# temp_sensor.net
KiCad netlist of a schematic drawn in EAGLE
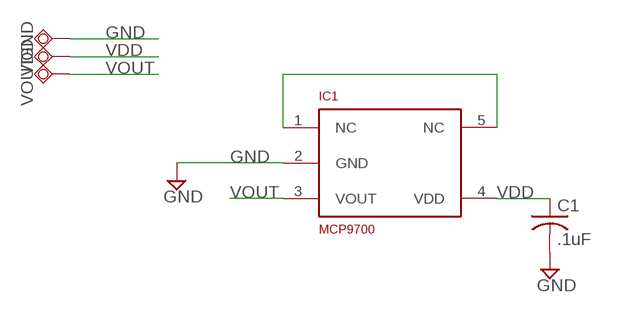
[diagram p0: schematic, sheet 1]

(export (version "E")
  (design (tool "Eeschema 10.0.6"))
  (components
    (comp (ref "C1")
      (value ".1uF")
      (footprint "eagle-import:C0805K")
      (libsource (lib "eagle-import") (part "C-USC0805K"))
    )
    (comp (ref "GND")
      (value "TPSQTP20SQ")
      (footprint "eagle-import:TP20SQ")
      (libsource (lib "eagle-import") (part "TPSQTP20SQ"))
    )
    (comp (ref "IC1")
      (value "MCP9700")
      (footprint "eagle-import:SC70")
      (libsource (lib "eagle-import") (part "MCP9700"))
    )
    (comp (ref "VDD")
      (value "TPSQTP20SQ")
      (footprint "eagle-import:TP20SQ")
      (libsource (lib "eagle-import") (part "TPSQTP20SQ"))
    )
    (comp (ref "VOUT")
      (value "TPSQTP20SQ")
      (footprint "eagle-import:TP20SQ")
      (libsource (lib "eagle-import") (part "TPSQTP20SQ"))
    )
  )
  (nets
    (net (code "1") (name "/VDD") (class "Default")
      (node (ref "C1") (pin "1") (pinfunction "1_1") (pintype "passive"))
      (node (ref "IC1") (pin "4") (pinfunction "VDD_4") (pintype "bidirectional"))
      (node (ref "VDD") (pin "TP") (pinfunction "TP_TP") (pintype "input"))
    )
    (net (code "2") (name "/VOUT") (class "Default")
      (node (ref "IC1") (pin "3") (pinfunction "VOUT_3") (pintype "bidirectional"))
      (node (ref "VOUT") (pin "TP") (pinfunction "TP_TP") (pintype "input"))
    )
    (net (code "3") (name "GND") (class "Default")
      (node (ref "C1") (pin "2") (pinfunction "2_2") (pintype "passive"))
      (node (ref "GND") (pin "TP") (pinfunction "TP_TP") (pintype "input"))
      (node (ref "IC1") (pin "2") (pinfunction "GND_2") (pintype "bidirectional"))
    )
    (net (code "4") (name "Net-(IC1-NC-Pad1)") (class "Default")
      (node (ref "IC1") (pin "1") (pinfunction "NC_1") (pintype "bidirectional"))
      (node (ref "IC1") (pin "5") (pinfunction "NC_5") (pintype "bidirectional"))
    )
  )
)
